# Peripherals.net
KiCad netlist of a schematic drawn in Altium Designer
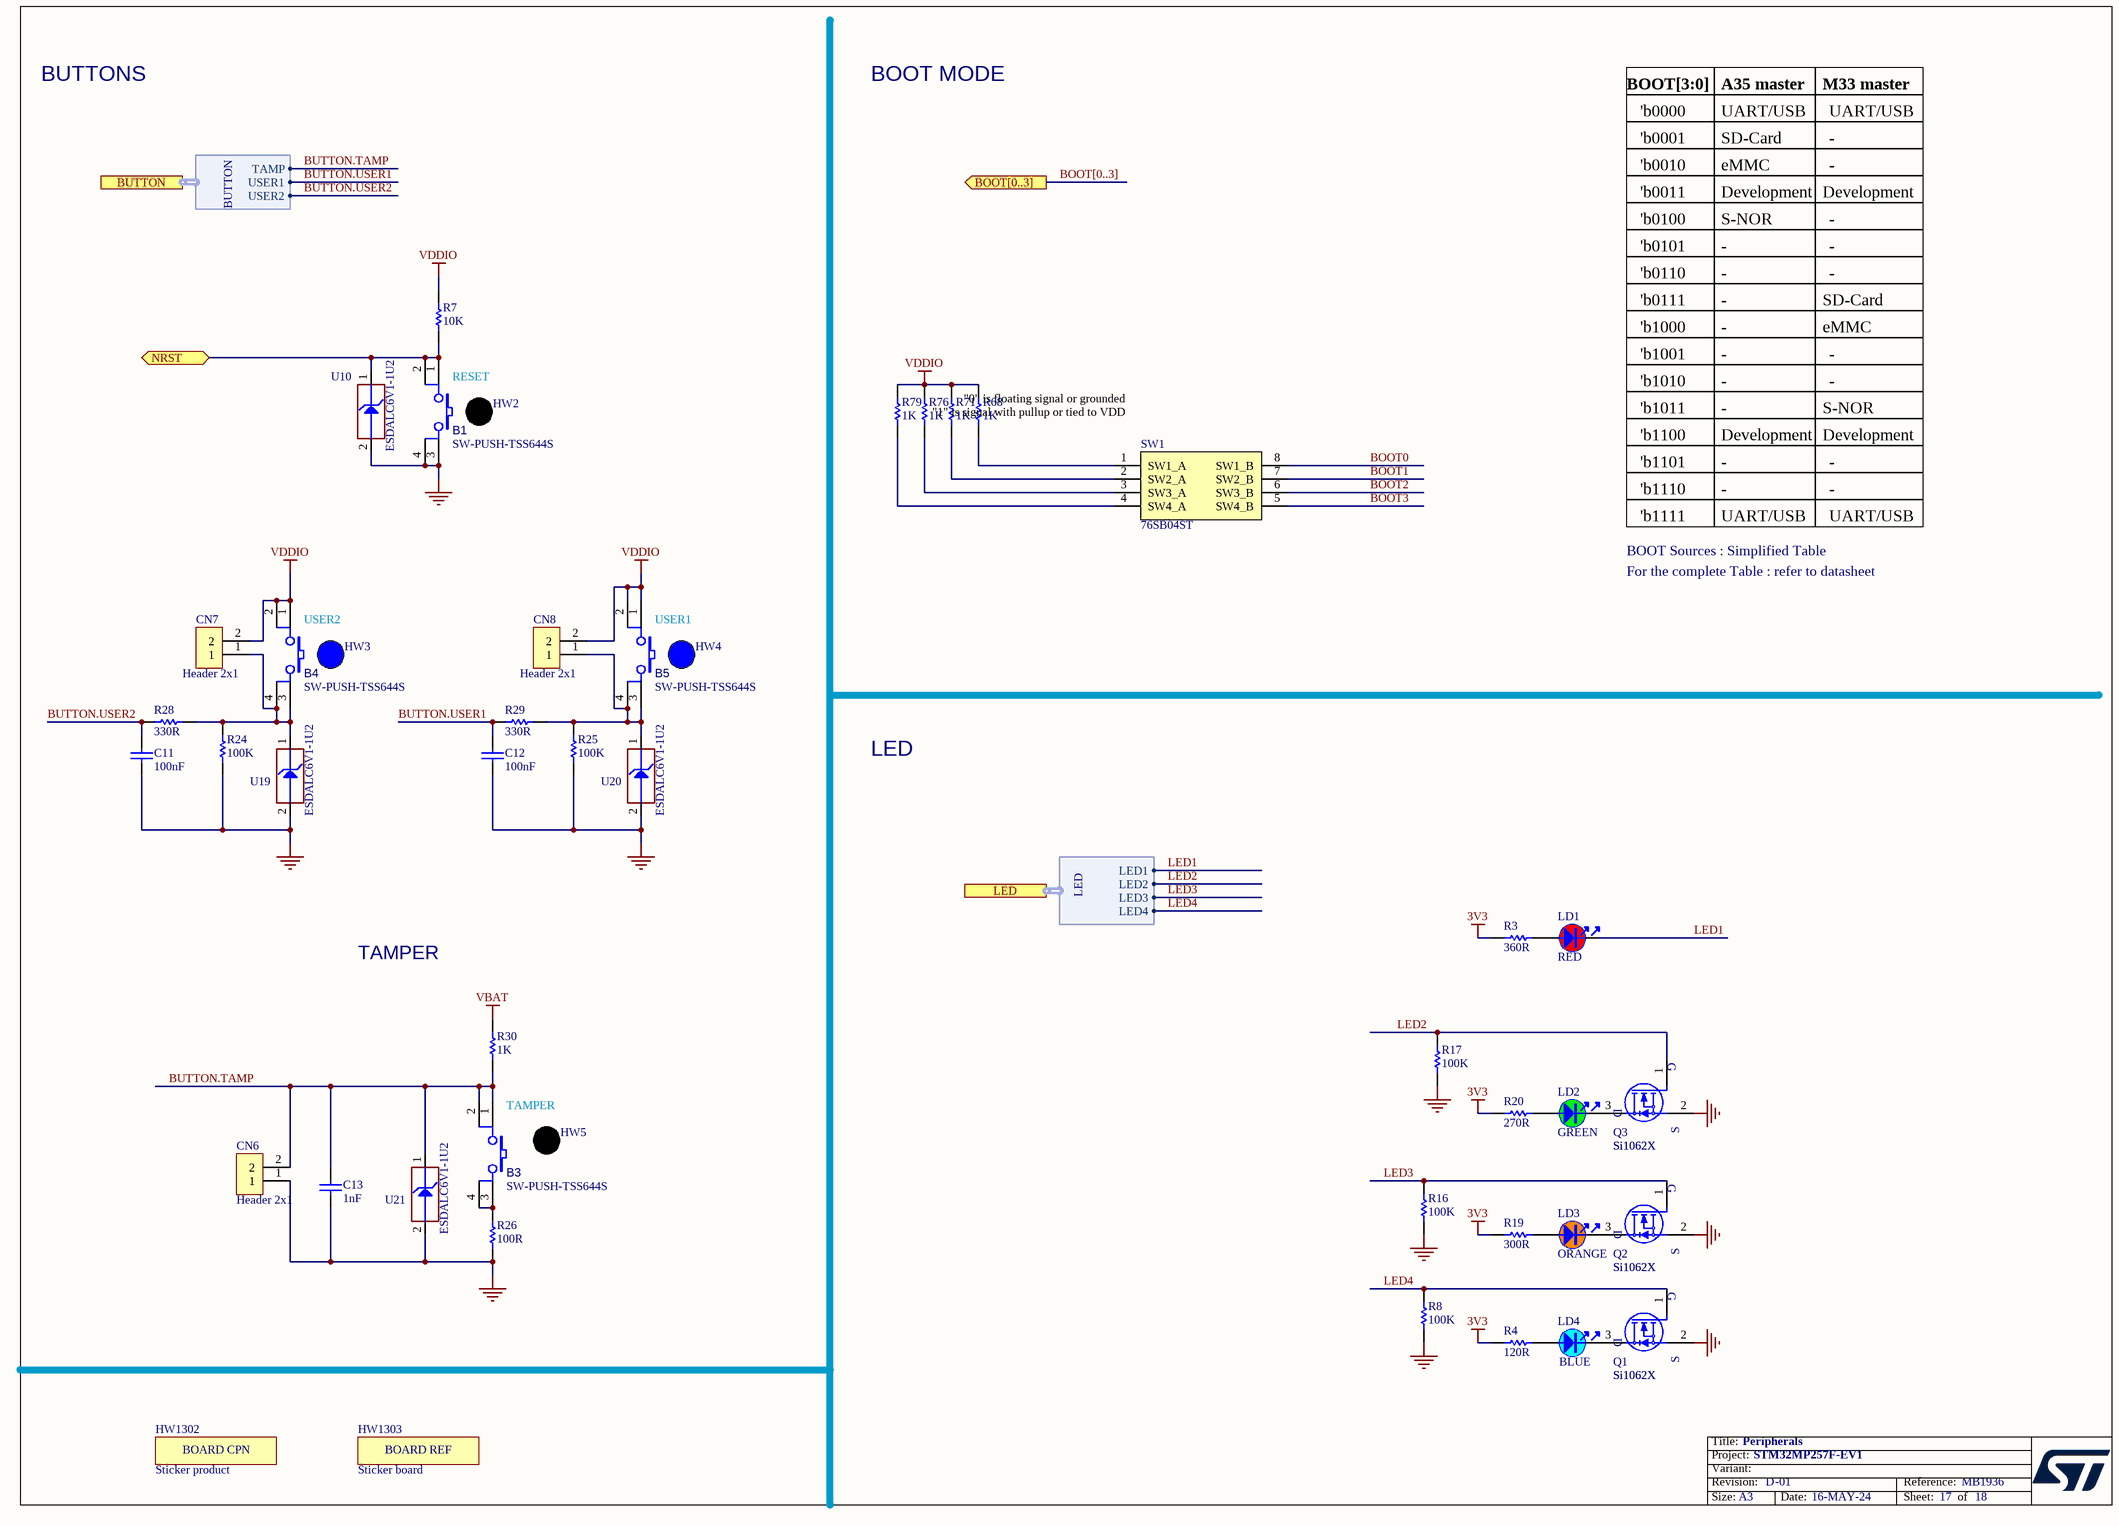
[diagram p0: Peripherals.SchDoc]

(export (version "E")
  (design (tool "Eeschema 10.0.6"))
  (components
    (comp (ref "B1")
      (value "SW-PUSH-TSS644S")
      (footprint "MCD_PARTS:SWI_KNITTER_TSS644S")
      (description "Push Button, NO, 0.05A, 12V, 2.6N, SMD, 9.0x6.2mm, T=7.3mm, changeable caps KTSC-6xx")
      (fields
        (field (name "INTERNAL_PART_NUMBER") "MCD-02417")
        (field (name "MANUFACTURER_PART_NUMBER") "TSS644S")
      )
      (libsource (lib "MCD_PARTS_database") (part "SW_PUSH_SMD"))
    )
    (comp (ref "B3")
      (value "SW-PUSH-TSS644S")
      (footprint "MCD_PARTS:SWI_KNITTER_TSS644S")
      (description "Push Button, NO, 0.05A, 12V, 2.6N, SMD, 9.0x6.2mm, T=7.3mm, changeable caps KTSC-6xx")
      (fields
        (field (name "INTERNAL_PART_NUMBER") "MCD-02417")
        (field (name "MANUFACTURER_PART_NUMBER") "TSS644S")
      )
      (libsource (lib "MCD_PARTS_database") (part "SW_PUSH_SMD"))
    )
    (comp (ref "B4")
      (value "SW-PUSH-TSS644S")
      (footprint "MCD_PARTS:SWI_KNITTER_TSS644S")
      (description "Push Button, NO, 0.05A, 12V, 2.6N, SMD, 9.0x6.2mm, T=7.3mm, changeable caps KTSC-6xx")
      (fields
        (field (name "INTERNAL_PART_NUMBER") "MCD-02417")
        (field (name "MANUFACTURER_PART_NUMBER") "TSS644S")
      )
      (libsource (lib "MCD_PARTS_database") (part "SW_PUSH_SMD"))
    )
    (comp (ref "B5")
      (value "SW-PUSH-TSS644S")
      (footprint "MCD_PARTS:SWI_KNITTER_TSS644S")
      (description "Push Button, NO, 0.05A, 12V, 2.6N, SMD, 9.0x6.2mm, T=7.3mm, changeable caps KTSC-6xx")
      (fields
        (field (name "INTERNAL_PART_NUMBER") "MCD-02417")
        (field (name "MANUFACTURER_PART_NUMBER") "TSS644S")
      )
      (libsource (lib "MCD_PARTS_database") (part "SW_PUSH_SMD"))
    )
    (comp (ref "C11")
      (value "100nF")
      (footprint "MCD_PARTS:C0402")
      (description "Capacitor, MLCC, 100nF, 16V, X7R, +/-10%, 0402, T=0.5mm")
      (fields
        (field (name "INTERNAL_PART_NUMBER") "MCD-00006")
        (field (name "MANUFACTURER_PART_NUMBER") "CC0402KRX7R7BB104")
      )
      (libsource (lib "MCD_PARTS_database") (part "Capacitor"))
    )
    (comp (ref "C12")
      (value "100nF")
      (footprint "MCD_PARTS:C0402")
      (description "Capacitor, MLCC, 100nF, 16V, X7R, +/-10%, 0402, T=0.5mm")
      (fields
        (field (name "INTERNAL_PART_NUMBER") "MCD-00006")
        (field (name "MANUFACTURER_PART_NUMBER") "CC0402KRX7R7BB104")
      )
      (libsource (lib "MCD_PARTS_database") (part "Capacitor"))
    )
    (comp (ref "C13")
      (value "1nF")
      (footprint "MCD_PARTS:C0402")
      (description "Capacitor, MLCC, 1nF, 16V, X7R, +/-10%, 0402, T=0.5mm")
      (fields (field (name "INTERNAL_PART_NUMBER") "MCD-00198") (field (name "MANUFACTURER") "YAGEO"))
      (libsource (lib "MCD_PARTS_database") (part "Capacitor"))
    )
    (comp (ref "CN6")
      (value "Header 2x1")
      (footprint "MCD_PARTS:CON_SAMTEC_TSW-102-07-G-S")
      (description "Header, 2x1, 2,54mm, VR, TH, Height 5.84mm/2.54mm")
      (fields (field (name "INTERNAL_PART_NUMBER") "MCD-00032") (field (name "MANUFACTURER") "SAMTEC"))
      (libsource (lib "MCD_PARTS_database") (part "Header 2x1"))
    )
    (comp (ref "CN7")
      (value "Header 2x1")
      (footprint "MCD_PARTS:CON_SAMTEC_TSW-102-07-G-S")
      (description "Header, 2x1, 2,54mm, VR, TH, Height 5.84mm/2.54mm")
      (fields (field (name "INTERNAL_PART_NUMBER") "MCD-00032") (field (name "MANUFACTURER") "SAMTEC"))
      (libsource (lib "MCD_PARTS_database") (part "Header 2x1"))
    )
    (comp (ref "CN8")
      (value "Header 2x1")
      (footprint "MCD_PARTS:CON_SAMTEC_TSW-102-07-G-S")
      (description "Header, 2x1, 2,54mm, VR, TH, Height 5.84mm/2.54mm")
      (fields (field (name "INTERNAL_PART_NUMBER") "MCD-00032") (field (name "MANUFACTURER") "SAMTEC"))
      (libsource (lib "MCD_PARTS_database") (part "Header 2x1"))
    )
    (comp (ref "HW2")
      (value "SW-CAP-KTSC-62K")
      (description "Black round cap for TSS6x series")
      (fields
        (field (name "INTERNAL_PART_NUMBER") "MCD-02420")
        (field (name "MANUFACTURER") "KNITTER-SWITCH")
      )
      (libsource (lib "MCD_PARTS_database") (part "SW-CAP-Black"))
    )
    (comp (ref "HW3")
      (value "Blue Hat")
      (description "Switch hat, blue, For KTSC-62B")
      (fields (field (name "INTERNAL_PART_NUMBER") "MCD-02136") (field (name "MANUFACTURER") "APEM INC"))
      (libsource (lib "MCD_PARTS_database") (part "BUTTON_HAT_BLUE"))
    )
    (comp (ref "HW4")
      (value "Blue Hat")
      (description "Switch hat, blue, For KTSC-62B")
      (fields (field (name "INTERNAL_PART_NUMBER") "MCD-02136") (field (name "MANUFACTURER") "APEM INC"))
      (libsource (lib "MCD_PARTS_database") (part "BUTTON_HAT_BLUE"))
    )
    (comp (ref "HW5")
      (value "SW-CAP-KTSC-62K")
      (description "Black round cap for TSS6x series")
      (fields
        (field (name "INTERNAL_PART_NUMBER") "MCD-02420")
        (field (name "MANUFACTURER") "KNITTER-SWITCH")
      )
      (libsource (lib "MCD_PARTS_database") (part "SW-CAP-Black"))
    )
    (comp (ref "HW1302")
      (value "Sticker product")
      (footprint "MCD_PARTS:STICKER_BOARD-CPN_25X5")
      (description "Sticker to mention board CPN code")
      (fields
        (field (name "INTERNAL_PART_NUMBER") "MCD-00547")
        (field (name "MANUFACTURER_PART_NUMBER") "n/a")
        (field (name "PROVIDED_BY") "SUBCO")
      )
      (libsource (lib "MCD_PARTS_database") (part "STICKER_BOARD_CPN"))
    )
    (comp (ref "HW1303")
      (value "Sticker board")
      (footprint "MCD_PARTS:STICKER_BOARD-REF_25X5")
      (description "Sticker to mention board reference + serial number")
      (fields
        (field (name "INTERNAL_PART_NUMBER") "MCD-00235")
        (field (name "MANUFACTURER_PART_NUMBER") "n/a")
        (field (name "PROVIDED_BY") "SUBCO")
      )
      (libsource (lib "MCD_PARTS_database") (part "STICKER_BOARD_REF"))
    )
    (comp (ref "LD1")
      (value "RED")
      (footprint "MCD_PARTS:LED_0603_VISHAY_VLMS1300-GS08_RED_1A2K_H0P8")
      (description "LED Red, 0603 SMD, 2V Forward Voltage")
      (fields
        (field (name "INTERNAL_PART_NUMBER") "MCD-00587")
        (field (name "MANUFACTURER_PART_NUMBER") "VLMS1300-GS08")
        (field (name "PROVIDED_BY") "SUBCO")
      )
      (libsource (lib "MCD_PARTS_database") (part "LED_red"))
    )
    (comp (ref "LD2")
      (value "GREEN")
      (footprint "MCD_PARTS:LED_0603_OSRAM_LG-Q396-PS-35_GREEN_1A2K_H0P4")
      (description "LED Green, 0603 SMD, Forward Voltage Typ=2V, Max=2.5V")
      (fields
        (field (name "INTERNAL_PART_NUMBER") "MCD-00588")
        (field (name "MANUFACTURER_PART_NUMBER") "LG Q396-PS-35")
        (field (name "PROVIDED_BY") "SUBCO")
      )
      (libsource (lib "MCD_PARTS_database") (part "LED_green"))
    )
    (comp (ref "LD3")
      (value "ORANGE")
      (footprint "MCD_PARTS:LED_0603_OSRAM_LO-Q976-PS-25_ORANGE_1A2K_H0P8")
      (description "LED Orange, 0603 SMD, Forward Voltage Min=1.6V, Max=2.4V")
      (fields
        (field (name "INTERNAL_PART_NUMBER") "MCD-00590")
        (field (name "MANUFACTURER_PART_NUMBER") "LO Q976-PS-25")
        (field (name "PROVIDED_BY") "SUBCO")
      )
      (libsource (lib "MCD_PARTS_database") (part "LED_orange"))
    )
    (comp (ref "LD4")
      (value "BLUE")
      (footprint "MCD_PARTS:LED_0603_OSRAM_LB-Q39G-L2OO-35-1_BLUE_1A2K_H0P4")
      (description "LED Blue, 0603 SMD, Forward Voltage Min=2,8V, Max=3,8V")
      (fields
        (field (name "INTERNAL_PART_NUMBER") "MCD-00585")
        (field (name "MANUFACTURER_PART_NUMBER") "LB Q39G-L2OO-35-1")
        (field (name "PROVIDED_BY") "SUBCO")
      )
      (libsource (lib "MCD_PARTS_database") (part "LED_blue"))
    )
    (comp (ref "Q1")
      (value "Si1062X")
      (footprint "MCD_PARTS:MOS_SC89-3L")
      (description "MOSFET N-CH 20V SC-89")
      (fields
        (field (name "INTERNAL_PART_NUMBER") "MCD-02221")
        (field (name "MANUFACTURER") "VISHAY")
        (field (name "MANUFACTURER_PART_NUMBER") "Si1062X")
      )
      (libsource (lib "MCD_PARTS_database") (part "MOSFET_N-CHANNEL"))
    )
    (comp (ref "Q2")
      (value "Si1062X")
      (footprint "MCD_PARTS:MOS_SC89-3L")
      (description "MOSFET N-CH 20V SC-89")
      (fields
        (field (name "INTERNAL_PART_NUMBER") "MCD-02221")
        (field (name "MANUFACTURER") "VISHAY")
        (field (name "MANUFACTURER_PART_NUMBER") "Si1062X")
      )
      (libsource (lib "MCD_PARTS_database") (part "MOSFET_N-CHANNEL"))
    )
    (comp (ref "Q3")
      (value "Si1062X")
      (footprint "MCD_PARTS:MOS_SC89-3L")
      (description "MOSFET N-CH 20V SC-89")
      (fields
        (field (name "INTERNAL_PART_NUMBER") "MCD-02221")
        (field (name "MANUFACTURER") "VISHAY")
        (field (name "MANUFACTURER_PART_NUMBER") "Si1062X")
      )
      (libsource (lib "MCD_PARTS_database") (part "MOSFET_N-CHANNEL"))
    )
    (comp (ref "R3")
      (value "360R")
      (footprint "MCD_PARTS:R0402")
      (description "Resistor,360R,0402,1%,1/16W")
      (fields
        (field (name "INTERNAL_PART_NUMBER") "MCD-00461")
        (field (name "MANUFACTURER_PART_NUMBER") "RC0402FR-07360RL")
        (field (name "PROVIDED_BY") "SUBCO")
      )
      (libsource (lib "MCD_PARTS_database") (part "Resistor"))
    )
    (comp (ref "R4")
      (value "120R")
      (footprint "MCD_PARTS:R0402")
      (description "Resistor,120R,0402,1%,1/16W")
      (fields
        (field (name "INTERNAL_PART_NUMBER") "MCD-00194")
        (field (name "MANUFACTURER_PART_NUMBER") "RC0402FR-07120RL")
        (field (name "PROVIDED_BY") "SUBCO")
      )
      (libsource (lib "MCD_PARTS_database") (part "Resistor"))
    )
    (comp (ref "R7")
      (value "10K")
      (footprint "MCD_PARTS:R0402")
      (description "Resistor,10K,0402,1%,1/16W")
      (fields
        (field (name "INTERNAL_PART_NUMBER") "MCD-00053")
        (field (name "MANUFACTURER_PART_NUMBER") "RC0402FR-0710KL")
      )
      (libsource (lib "MCD_PARTS_database") (part "Resistor"))
    )
    (comp (ref "R8")
      (value "100K")
      (footprint "MCD_PARTS:R0402")
      (description "Resistor,100K,0402,1%,1/16W")
      (fields
        (field (name "INTERNAL_PART_NUMBER") "MCD-00059")
        (field (name "MANUFACTURER_PART_NUMBER") "RC0402FR-07100KL")
      )
      (libsource (lib "MCD_PARTS_database") (part "Resistor"))
    )
    (comp (ref "R16")
      (value "100K")
      (footprint "MCD_PARTS:R0402")
      (description "Resistor,100K,0402,1%,1/16W")
      (fields
        (field (name "INTERNAL_PART_NUMBER") "MCD-00059")
        (field (name "MANUFACTURER_PART_NUMBER") "RC0402FR-07100KL")
      )
      (libsource (lib "MCD_PARTS_database") (part "Resistor"))
    )
    (comp (ref "R17")
      (value "100K")
      (footprint "MCD_PARTS:R0402")
      (description "Resistor,100K,0402,1%,1/16W")
      (fields
        (field (name "INTERNAL_PART_NUMBER") "MCD-00059")
        (field (name "MANUFACTURER_PART_NUMBER") "RC0402FR-07100KL")
      )
      (libsource (lib "MCD_PARTS_database") (part "Resistor"))
    )
    (comp (ref "R19")
      (value "300R")
      (footprint "MCD_PARTS:R0402")
      (description "Resistor,300R,0402,1%,1/16W")
      (fields
        (field (name "INTERNAL_PART_NUMBER") "MCD-00449")
        (field (name "MANUFACTURER_PART_NUMBER") "RC0402FR-07300RL")
        (field (name "PROVIDED_BY") "SUBCO")
      )
      (libsource (lib "MCD_PARTS_database") (part "Resistor"))
    )
    (comp (ref "R20")
      (value "270R")
      (footprint "MCD_PARTS:R0402")
      (description "Resistor,270R,0402,1%,1/16W")
      (fields
        (field (name "INTERNAL_PART_NUMBER") "MCD-00441")
        (field (name "MANUFACTURER_PART_NUMBER") "RC0402FR-07270RL")
        (field (name "PROVIDED_BY") "SUBCO")
      )
      (libsource (lib "MCD_PARTS_database") (part "Resistor"))
    )
    (comp (ref "R24")
      (value "100K")
      (footprint "MCD_PARTS:R0402")
      (description "Resistor,100K,0402,1%,1/16W")
      (fields
        (field (name "INTERNAL_PART_NUMBER") "MCD-00059")
        (field (name "MANUFACTURER_PART_NUMBER") "RC0402FR-07100KL")
      )
      (libsource (lib "MCD_PARTS_database") (part "Resistor"))
    )
    (comp (ref "R25")
      (value "100K")
      (footprint "MCD_PARTS:R0402")
      (description "Resistor,100K,0402,1%,1/16W")
      (fields
        (field (name "INTERNAL_PART_NUMBER") "MCD-00059")
        (field (name "MANUFACTURER_PART_NUMBER") "RC0402FR-07100KL")
      )
      (libsource (lib "MCD_PARTS_database") (part "Resistor"))
    )
    (comp (ref "R26")
      (value "100R")
      (footprint "MCD_PARTS:R0402")
      (description "Resistor, 100R, 0402, +/- 1%, 1/16W")
      (fields
        (field (name "INTERNAL_PART_NUMBER") "MCD-00067")
        (field (name "MANUFACTURER_PART_NUMBER") "RC0402FR-07100RL")
      )
      (libsource (lib "MCD_PARTS_database") (part "Resistor"))
    )
    (comp (ref "R28")
      (value "330R")
      (footprint "MCD_PARTS:R0402")
      (description "Resistor,330R,0402,1%,1/16W")
      (fields
        (field (name "INTERNAL_PART_NUMBER") "MCD-00062")
        (field (name "MANUFACTURER_PART_NUMBER") "RC0402FR-07330RL")
      )
      (libsource (lib "MCD_PARTS_database") (part "Resistor"))
    )
    (comp (ref "R29")
      (value "330R")
      (footprint "MCD_PARTS:R0402")
      (description "Resistor,330R,0402,1%,1/16W")
      (fields
        (field (name "INTERNAL_PART_NUMBER") "MCD-00062")
        (field (name "MANUFACTURER_PART_NUMBER") "RC0402FR-07330RL")
      )
      (libsource (lib "MCD_PARTS_database") (part "Resistor"))
    )
    (comp (ref "R30")
      (value "1K")
      (footprint "MCD_PARTS:R0402")
      (description "Resistor, 1K, 0402, +/-1%,1/16W")
      (fields
        (field (name "INTERNAL_PART_NUMBER") "MCD-00061")
        (field (name "MANUFACTURER_PART_NUMBER") "RC0402FR-071KL")
      )
      (libsource (lib "MCD_PARTS_database") (part "Resistor"))
    )
    (comp (ref "R68")
      (value "1K")
      (footprint "MCD_PARTS:R0402")
      (description "Resistor,1K,0402,1%,1/16W")
      (fields (field (name "INTERNAL_PART_NUMBER") "MCD-00061") (field (name "MANUFACTURER") "YAGEO"))
      (libsource (lib "MCD_PARTS_database") (part "Resistor"))
    )
    (comp (ref "R71")
      (value "1K")
      (footprint "MCD_PARTS:R0402")
      (description "Resistor,1K,0402,1%,1/16W")
      (fields (field (name "INTERNAL_PART_NUMBER") "MCD-00061") (field (name "MANUFACTURER") "YAGEO"))
      (libsource (lib "MCD_PARTS_database") (part "Resistor"))
    )
    (comp (ref "R76")
      (value "1K")
      (footprint "MCD_PARTS:R0402")
      (description "Resistor,1K,0402,1%,1/16W")
      (fields (field (name "INTERNAL_PART_NUMBER") "MCD-00061") (field (name "MANUFACTURER") "YAGEO"))
      (libsource (lib "MCD_PARTS_database") (part "Resistor"))
    )
    (comp (ref "R79")
      (value "1K")
      (footprint "MCD_PARTS:R0402")
      (description "Resistor,1K,0402,1%,1/16W")
      (fields (field (name "INTERNAL_PART_NUMBER") "MCD-00061") (field (name "MANUFACTURER") "YAGEO"))
      (libsource (lib "MCD_PARTS_database") (part "Resistor"))
    )
    (comp (ref "SW1")
      (value "76SB04ST")
      (footprint "MCD_PARTS:SWI_GRAYHILL-INC_76SB04ST")
      (description "Quad SPST switch, TH, 2.54mm pitch, height 7.5mm")
      (fields (field (name "INTERNAL_PART_NUMBER") "MCD-02256") (field (name "MANUFACTURER") "GRAYHILL"))
      (libsource (lib "MCD_PARTS_database") (part "76SB04ST"))
    )
    (comp (ref "U10")
      (value "ESDALC6V1-1U2")
      (footprint "MCD_PARTS:ESD_ST0201")
      (description "ESD protection 6V1")
      (fields
        (field (name "INTERNAL_PART_NUMBER") "MCD-00170")
        (field (name "MANUFACTURER") "STMICROELECTRONICS")
      )
      (libsource (lib "MCD_PARTS_database") (part "ESD-TRANSIL"))
    )
    (comp (ref "U19")
      (value "ESDALC6V1-1U2")
      (footprint "MCD_PARTS:ESD_ST0201")
      (description "ESD protection 6V1")
      (fields
        (field (name "INTERNAL_PART_NUMBER") "MCD-00170")
        (field (name "MANUFACTURER") "STMICROELECTRONICS")
      )
      (libsource (lib "MCD_PARTS_database") (part "ESD-TRANSIL"))
    )
    (comp (ref "U20")
      (value "ESDALC6V1-1U2")
      (footprint "MCD_PARTS:ESD_ST0201")
      (description "ESD protection 6V1")
      (fields
        (field (name "INTERNAL_PART_NUMBER") "MCD-00170")
        (field (name "MANUFACTURER") "STMICROELECTRONICS")
      )
      (libsource (lib "MCD_PARTS_database") (part "ESD-TRANSIL"))
    )
    (comp (ref "U21")
      (value "ESDALC6V1-1U2")
      (footprint "MCD_PARTS:ESD_ST0201")
      (description "ESD protection 6V1")
      (fields
        (field (name "INTERNAL_PART_NUMBER") "MCD-00170")
        (field (name "MANUFACTURER") "STMICROELECTRONICS")
      )
      (libsource (lib "MCD_PARTS_database") (part "ESD-TRANSIL"))
    )
  )
  (nets
    (net (code "3") (name "/BOOT0") (class "Default")
      (node (ref "SW1") (pin "8") (pinfunction "SW1_B_8") (pintype "passive"))
    )
    (net (code "4") (name "/BOOT1") (class "Default")
      (node (ref "SW1") (pin "7") (pinfunction "SW2_B_7") (pintype "passive"))
    )
    (net (code "5") (name "/BOOT2") (class "Default")
      (node (ref "SW1") (pin "6") (pinfunction "SW3_B_6") (pintype "passive"))
    )
    (net (code "6") (name "/BOOT3") (class "Default")
      (node (ref "SW1") (pin "5") (pinfunction "SW4_B_5") (pintype "passive"))
    )
    (net (code "8") (name "/BUTTON.TAMP") (class "Default")
      (node (ref "B3") (pin "1") (pinfunction "1_1") (pintype "passive"))
      (node (ref "B3") (pin "2") (pinfunction "2_2") (pintype "passive"))
      (node (ref "C13") (pin "2") (pinfunction "2_2") (pintype "passive"))
      (node (ref "CN6") (pin "2") (pinfunction "2_2") (pintype "passive"))
      (node (ref "R30") (pin "1") (pinfunction "1_1") (pintype "passive"))
      (node (ref "U21") (pin "1") (pinfunction "IO1_1") (pintype "passive"))
    )
    (net (code "9") (name "/BUTTON.USER1") (class "Default")
      (node (ref "C12") (pin "2") (pinfunction "2_2") (pintype "passive"))
      (node (ref "R29") (pin "1") (pinfunction "1_1") (pintype "passive"))
    )
    (net (code "10") (name "/BUTTON.USER2") (class "Default")
      (node (ref "C11") (pin "2") (pinfunction "2_2") (pintype "passive"))
      (node (ref "R28") (pin "1") (pinfunction "1_1") (pintype "passive"))
    )
    (net (code "11") (name "/LED1") (class "Default") (node (ref "LD1") (pin "2") (pintype "passive")))
    (net (code "12") (name "/LED2") (class "Default")
      (node (ref "Q3") (pin "1") (pinfunction "G_1") (pintype "passive"))
      (node (ref "R17") (pin "2") (pinfunction "2_2") (pintype "passive"))
    )
    (net (code "13") (name "/LED3") (class "Default")
      (node (ref "Q2") (pin "1") (pinfunction "G_1") (pintype "passive"))
      (node (ref "R16") (pin "2") (pinfunction "2_2") (pintype "passive"))
    )
    (net (code "14") (name "/LED4") (class "Default")
      (node (ref "Q1") (pin "1") (pinfunction "G_1") (pintype "passive"))
      (node (ref "R8") (pin "2") (pinfunction "2_2") (pintype "passive"))
    )
    (net (code "15") (name "/NRST") (class "Default")
      (node (ref "B1") (pin "1") (pinfunction "1_1") (pintype "passive"))
      (node (ref "B1") (pin "2") (pinfunction "2_2") (pintype "passive"))
      (node (ref "R7") (pin "1") (pinfunction "1_1") (pintype "passive"))
      (node (ref "U10") (pin "1") (pinfunction "IO1_1") (pintype "passive"))
    )
    (net (code "18") (name "3V3") (class "Default")
      (node (ref "R19") (pin "2") (pinfunction "2_2") (pintype "passive"))
      (node (ref "R20") (pin "2") (pinfunction "2_2") (pintype "passive"))
      (node (ref "R3") (pin "1") (pinfunction "1_1") (pintype "passive"))
      (node (ref "R4") (pin "1") (pinfunction "1_1") (pintype "passive"))
    )
    (net (code "19") (name "GND") (class "Default")
      (node (ref "B1") (pin "3") (pinfunction "3_3") (pintype "passive"))
      (node (ref "B1") (pin "4") (pinfunction "4_4") (pintype "passive"))
      (node (ref "C11") (pin "1") (pinfunction "1_1") (pintype "passive"))
      (node (ref "C12") (pin "1") (pinfunction "1_1") (pintype "passive"))
      (node (ref "C13") (pin "1") (pinfunction "1_1") (pintype "passive"))
      (node (ref "CN6") (pin "1") (pinfunction "1_1") (pintype "passive"))
      (node (ref "Q1") (pin "2") (pinfunction "S_2") (pintype "passive"))
      (node (ref "Q2") (pin "2") (pinfunction "S_2") (pintype "passive"))
      (node (ref "Q3") (pin "2") (pinfunction "S_2") (pintype "passive"))
      (node (ref "R16") (pin "1") (pinfunction "1_1") (pintype "passive"))
      (node (ref "R17") (pin "1") (pinfunction "1_1") (pintype "passive"))
      (node (ref "R24") (pin "1") (pinfunction "1_1") (pintype "passive"))
      (node (ref "R25") (pin "1") (pinfunction "1_1") (pintype "passive"))
      (node (ref "R26") (pin "2") (pinfunction "2_2") (pintype "passive"))
      (node (ref "R8") (pin "1") (pinfunction "1_1") (pintype "passive"))
      (node (ref "U10") (pin "2") (pinfunction "GND_2") (pintype "passive"))
      (node (ref "U19") (pin "2") (pinfunction "GND_2") (pintype "passive"))
      (node (ref "U20") (pin "2") (pinfunction "GND_2") (pintype "passive"))
      (node (ref "U21") (pin "2") (pinfunction "GND_2") (pintype "passive"))
    )
    (net (code "20") (name "Net-(B3-Pad3)") (class "Default")
      (node (ref "B3") (pin "3") (pinfunction "3_3") (pintype "passive"))
      (node (ref "B3") (pin "4") (pinfunction "4_4") (pintype "passive"))
      (node (ref "R26") (pin "1") (pinfunction "1_1") (pintype "passive"))
    )
    (net (code "21") (name "Net-(LD1-Pad1)") (class "Default")
      (node (ref "LD1") (pin "1") (pintype "passive"))
      (node (ref "R3") (pin "2") (pinfunction "2_2") (pintype "passive"))
    )
    (net (code "22") (name "Net-(LD2-Pad1)") (class "Default")
      (node (ref "LD2") (pin "1") (pintype "passive"))
      (node (ref "R20") (pin "1") (pinfunction "1_1") (pintype "passive"))
    )
    (net (code "23") (name "Net-(LD3-Pad1)") (class "Default")
      (node (ref "LD3") (pin "1") (pintype "passive"))
      (node (ref "R19") (pin "1") (pinfunction "1_1") (pintype "passive"))
    )
    (net (code "24") (name "Net-(LD4-Pad1)") (class "Default")
      (node (ref "LD4") (pin "1") (pintype "passive"))
      (node (ref "R4") (pin "2") (pinfunction "2_2") (pintype "passive"))
    )
    (net (code "25") (name "Net-(Q1-D)") (class "Default")
      (node (ref "LD4") (pin "2") (pintype "passive"))
      (node (ref "Q1") (pin "3") (pinfunction "D_3") (pintype "passive"))
    )
    (net (code "26") (name "Net-(Q2-D)") (class "Default")
      (node (ref "LD3") (pin "2") (pintype "passive"))
      (node (ref "Q2") (pin "3") (pinfunction "D_3") (pintype "passive"))
    )
    (net (code "27") (name "Net-(Q3-D)") (class "Default")
      (node (ref "LD2") (pin "2") (pintype "passive"))
      (node (ref "Q3") (pin "3") (pinfunction "D_3") (pintype "passive"))
    )
    (net (code "28") (name "Net-(SW1-SW1_A)") (class "Default")
      (node (ref "R68") (pin "1") (pinfunction "1_1") (pintype "passive"))
      (node (ref "SW1") (pin "1") (pinfunction "SW1_A_1") (pintype "passive"))
    )
    (net (code "29") (name "Net-(SW1-SW2_A)") (class "Default")
      (node (ref "R71") (pin "1") (pinfunction "1_1") (pintype "passive"))
      (node (ref "SW1") (pin "2") (pinfunction "SW2_A_2") (pintype "passive"))
    )
    (net (code "30") (name "Net-(SW1-SW3_A)") (class "Default")
      (node (ref "R76") (pin "1") (pinfunction "1_1") (pintype "passive"))
      (node (ref "SW1") (pin "3") (pinfunction "SW3_A_3") (pintype "passive"))
    )
    (net (code "31") (name "Net-(SW1-SW4_A)") (class "Default")
      (node (ref "R79") (pin "1") (pinfunction "1_1") (pintype "passive"))
      (node (ref "SW1") (pin "4") (pinfunction "SW4_A_4") (pintype "passive"))
    )
    (net (code "32") (name "Net-(U19-IO1)") (class "Default")
      (node (ref "B4") (pin "3") (pinfunction "3_3") (pintype "passive"))
      (node (ref "B4") (pin "4") (pinfunction "4_4") (pintype "passive"))
      (node (ref "CN7") (pin "1") (pinfunction "1_1") (pintype "passive"))
      (node (ref "R24") (pin "2") (pinfunction "2_2") (pintype "passive"))
      (node (ref "R28") (pin "2") (pinfunction "2_2") (pintype "passive"))
      (node (ref "U19") (pin "1") (pinfunction "IO1_1") (pintype "passive"))
    )
    (net (code "33") (name "Net-(U20-IO1)") (class "Default")
      (node (ref "B5") (pin "3") (pinfunction "3_3") (pintype "passive"))
      (node (ref "B5") (pin "4") (pinfunction "4_4") (pintype "passive"))
      (node (ref "CN8") (pin "1") (pinfunction "1_1") (pintype "passive"))
      (node (ref "R25") (pin "2") (pinfunction "2_2") (pintype "passive"))
      (node (ref "R29") (pin "2") (pinfunction "2_2") (pintype "passive"))
      (node (ref "U20") (pin "1") (pinfunction "IO1_1") (pintype "passive"))
    )
    (net (code "34") (name "VBAT") (class "Default")
      (node (ref "R30") (pin "2") (pinfunction "2_2") (pintype "passive"))
    )
    (net (code "35") (name "VDDIO") (class "Default")
      (node (ref "B4") (pin "1") (pinfunction "1_1") (pintype "passive"))
      (node (ref "B4") (pin "2") (pinfunction "2_2") (pintype "passive"))
      (node (ref "B5") (pin "1") (pinfunction "1_1") (pintype "passive"))
      (node (ref "B5") (pin "2") (pinfunction "2_2") (pintype "passive"))
      (node (ref "CN7") (pin "2") (pinfunction "2_2") (pintype "passive"))
      (node (ref "CN8") (pin "2") (pinfunction "2_2") (pintype "passive"))
      (node (ref "R68") (pin "2") (pinfunction "2_2") (pintype "passive"))
      (node (ref "R7") (pin "2") (pinfunction "2_2") (pintype "passive"))
      (node (ref "R71") (pin "2") (pinfunction "2_2") (pintype "passive"))
      (node (ref "R76") (pin "2") (pinfunction "2_2") (pintype "passive"))
      (node (ref "R79") (pin "2") (pinfunction "2_2") (pintype "passive"))
    )
  )
)
